# interstage_A1.net
KiCad netlist of a schematic drawn in EAGLE
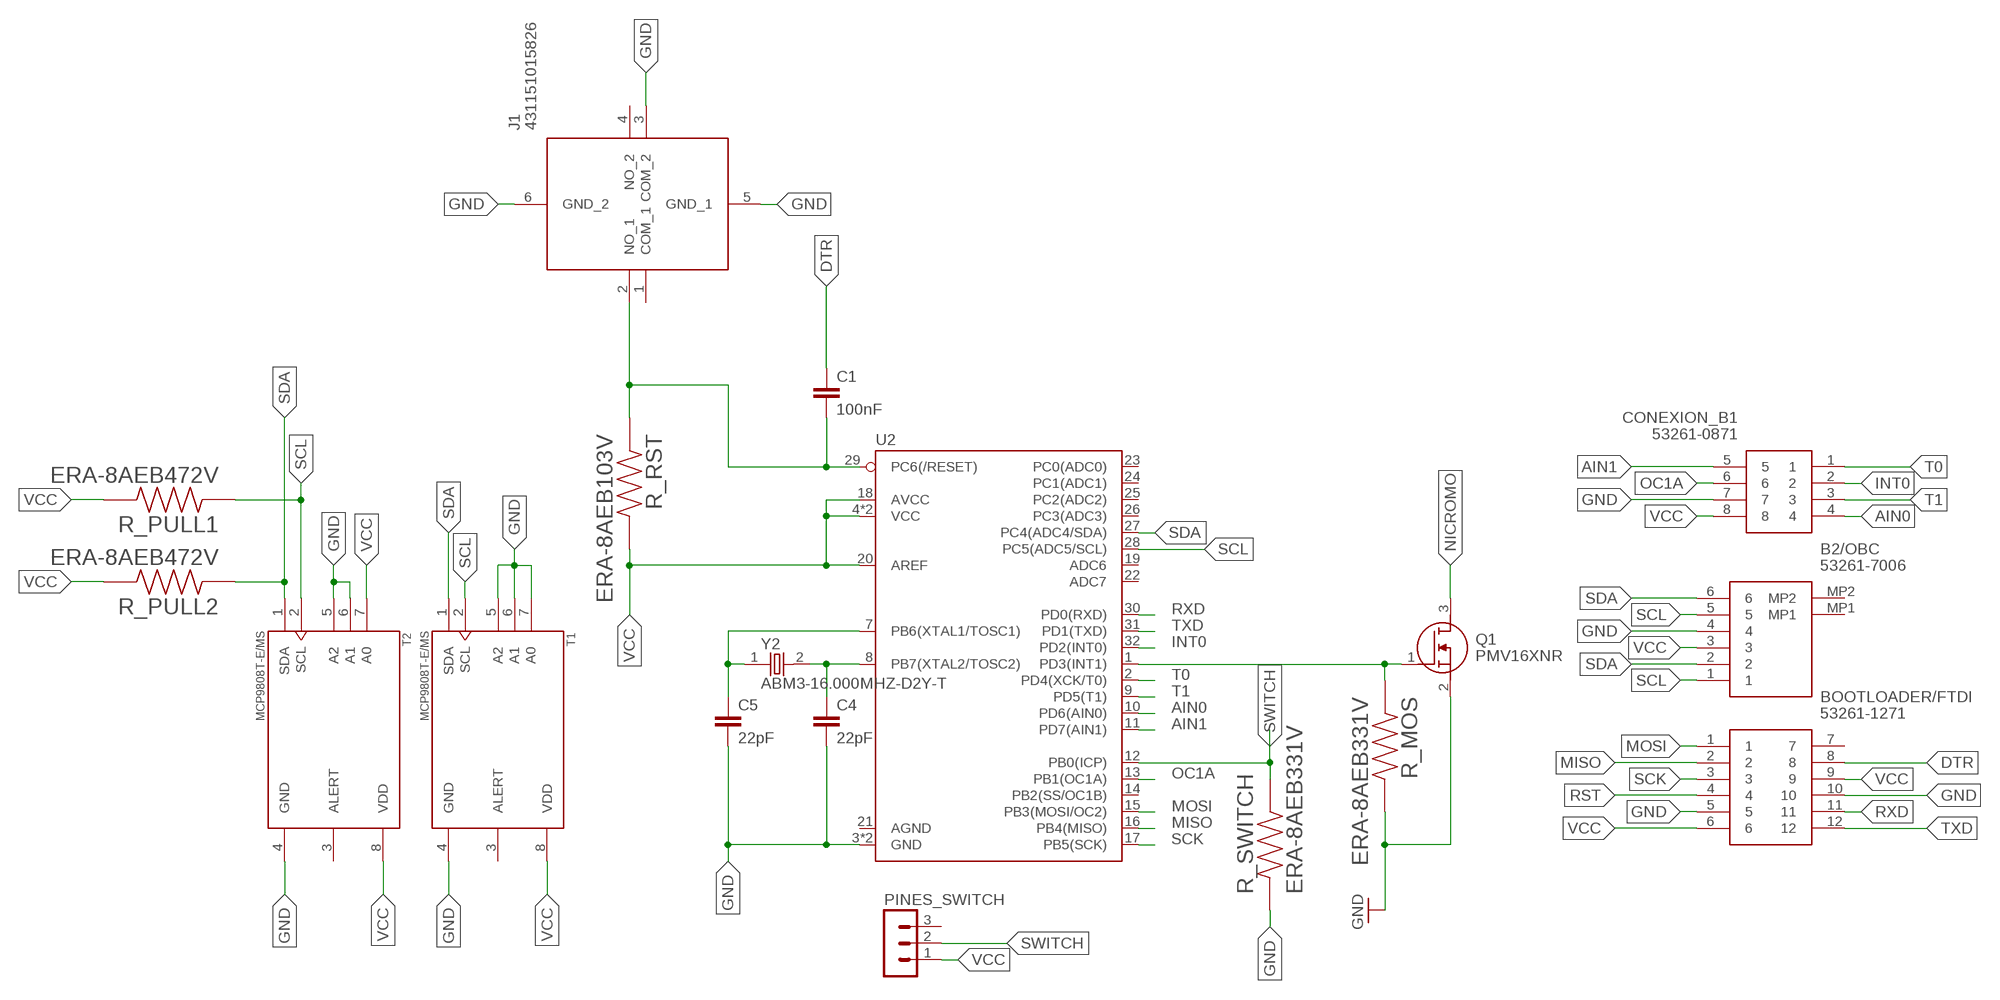
[diagram p0: schematic, sheet 1]

(export (version "E")
  (design (tool "Eeschema 10.0.6"))
  (components
    (comp (ref "B2/OBC")
      (value "53261-7006")
      (footprint "eagle-import:532617006")
      (fields (field (name "MOUSER_PART_NUMBER") "538-53261-7006"))
      (libsource (lib "eagle-import") (part "53261-7006"))
    )
    (comp (ref "BOOTLOADER/FTDI")
      (value "53261-1271")
      (footprint "eagle-import:53261-1271")
      (fields (field (name "MOUSER_PART_NUMBER") "538-53261-1271"))
      (libsource (lib "eagle-import") (part "53261-1271"))
    )
    (comp (ref "C1")
      (value "100nF")
      (footprint "eagle-import:C0805K")
      (libsource (lib "eagle-import") (part "C-EUC0805K"))
    )
    (comp (ref "C4")
      (value "22pF")
      (footprint "eagle-import:C0603K")
      (libsource (lib "eagle-import") (part "C-EUC0603K"))
    )
    (comp (ref "C5")
      (value "22pF")
      (footprint "eagle-import:C0603K")
      (libsource (lib "eagle-import") (part "C-EUC0603K"))
    )
    (comp (ref "CONEXION_B1")
      (value "53261-0871")
      (footprint "eagle-import:53261-0871")
      (fields (field (name "MOUSER_PART_NUMBER") "538-53261-0871"))
      (libsource (lib "eagle-import") (part "53261-0871"))
    )
    (comp (ref "J1")
      (value "431151015826")
      (footprint "eagle-import:431151015826")
      (fields (field (name "MOUSER_PART_NUMBER") "710-431151015826"))
      (libsource (lib "eagle-import") (part "431151015826"))
    )
    (comp (ref "PINES_SWITCH")
      (value "MA03-1")
      (footprint "eagle-import:MA03-1")
      (libsource (lib "eagle-import") (part "MA03-1"))
    )
    (comp (ref "Q1")
      (value "PMV16XNR")
      (footprint "eagle-import:SOT95P230X110-3N")
      (fields (field (name "MOUSER_PART_NUMBER") "771-PMV16XNR"))
      (libsource (lib "eagle-import") (part "PMV16XNR"))
    )
    (comp (ref "R_MOS")
      (value "ERA-8AEB331V")
      (footprint "eagle-import:RESC3216X70N")
      (fields (field (name "DIGI-KEY_PART_NUMBER") "P330BCCT-ND") (field (name "MF") "Panasonic Electronic"))
      (libsource (lib "eagle-import") (part "ERA-8AEB331V"))
    )
    (comp (ref "R_PULL1")
      (value "ERA-8AEB472V")
      (footprint "eagle-import:RESC3216X70N")
      (fields (field (name "DIGI-KEY_PART_NUMBER") "P4.7KBCCT-ND") (field (name "MF") "Panasonic"))
      (libsource (lib "eagle-import") (part "ERA-8AEB472V"))
    )
    (comp (ref "R_PULL2")
      (value "ERA-8AEB472V")
      (footprint "eagle-import:RESC3216X70N")
      (fields (field (name "DIGI-KEY_PART_NUMBER") "P4.7KBCCT-ND") (field (name "MF") "Panasonic"))
      (libsource (lib "eagle-import") (part "ERA-8AEB472V"))
    )
    (comp (ref "R_RST")
      (value "ERA-8AEB103V")
      (footprint "eagle-import:RESC3216X70N")
      (fields
        (field (name "DIGI-KEY_PART_NUMBER") "P10KBCCT-ND")
        (field (name "MF") "Panasonic Electronic Components")
      )
      (libsource (lib "eagle-import") (part "ERA-8AEB103V"))
    )
    (comp (ref "R_SWITCH")
      (value "ERA-8AEB331V")
      (footprint "eagle-import:RESC3216X70N")
      (fields (field (name "DIGI-KEY_PART_NUMBER") "P330BCCT-ND") (field (name "MF") "Panasonic Electronic"))
      (libsource (lib "eagle-import") (part "ERA-8AEB331V"))
    )
    (comp (ref "T1")
      (value "MCP9808T-E/MS")
      (footprint "eagle-import:SOP65P490X110-8N")
      (fields (field (name "DIGI-KEY_PART_NUMBER") "MCP9808T-E/MSCT-ND") (field (name "MF") "Microchip"))
      (libsource (lib "eagle-import") (part "MCP9808T-E/MS"))
    )
    (comp (ref "T2")
      (value "MCP9808T-E/MS")
      (footprint "eagle-import:SOP65P490X110-8N")
      (fields (field (name "DIGI-KEY_PART_NUMBER") "MCP9808T-E/MSCT-ND") (field (name "MF") "Microchip"))
      (libsource (lib "eagle-import") (part "MCP9808T-E/MS"))
    )
    (comp (ref "U2")
      (value "ATMEGA328P_TQFP")
      (footprint "eagle-import:TQFP32-08")
      (libsource (lib "eagle-import") (part "ATMEGA328P_TQFP"))
    )
    (comp (ref "Y2")
      (value "ABM3-16.000MHZ-D2Y-T")
      (footprint "eagle-import:XTAL500X320X130N")
      (fields (field (name "DIGI-KEY_PART_NUMBER") "535-10638-1-ND") (field (name "MF") "Abracon"))
      (libsource (lib "eagle-import") (part "ABM3-16.000MHZ-D2Y-T"))
    )
  )
  (nets
    (net (code "1") (name "AIN0") (class "Default")
      (node (ref "CONEXION_B1") (pin "4") (pinfunction "4_4") (pintype "bidirectional"))
      (node (ref "U2") (pin "10") (pinfunction "PD6(AIN0)_10") (pintype "bidirectional"))
    )
    (net (code "2") (name "AIN1") (class "Default")
      (node (ref "CONEXION_B1") (pin "5") (pinfunction "5_5") (pintype "bidirectional"))
      (node (ref "U2") (pin "11") (pinfunction "PD7(AIN1)_11") (pintype "bidirectional"))
    )
    (net (code "3") (name "DTR") (class "Default")
      (node (ref "BOOTLOADER/FTDI") (pin "8") (pinfunction "8_8") (pintype "bidirectional"))
      (node (ref "C1") (pin "1") (pinfunction "1_1") (pintype "passive"))
    )
    (net (code "4") (name "GND") (class "Default")
      (node (ref "B2/OBC") (pin "4") (pinfunction "4_4") (pintype "bidirectional"))
      (node (ref "BOOTLOADER/FTDI") (pin "10") (pinfunction "10_10") (pintype "bidirectional"))
      (node (ref "BOOTLOADER/FTDI") (pin "5") (pinfunction "5_5") (pintype "bidirectional"))
      (node (ref "C4") (pin "2") (pinfunction "2_2") (pintype "passive"))
      (node (ref "C5") (pin "2") (pinfunction "2_2") (pintype "passive"))
      (node (ref "CONEXION_B1") (pin "7") (pinfunction "7_7") (pintype "bidirectional"))
      (node (ref "J1") (pin "3") (pinfunction "COM_2_3") (pintype "bidirectional"))
      (node (ref "J1") (pin "5") (pinfunction "GND_1_5") (pintype "bidirectional"))
      (node (ref "J1") (pin "6") (pinfunction "GND_2_6") (pintype "bidirectional"))
      (node (ref "Q1") (pin "2") (pinfunction "S_2") (pintype "bidirectional"))
      (node (ref "R_MOS") (pin "2") (pinfunction "2_2") (pintype "passive"))
      (node (ref "R_SWITCH") (pin "1") (pinfunction "1_1") (pintype "passive"))
      (node (ref "T1") (pin "4") (pinfunction "GND_4") (pintype "power_in"))
      (node (ref "T1") (pin "5") (pinfunction "A2_5") (pintype "input"))
      (node (ref "T1") (pin "6") (pinfunction "A1_6") (pintype "input"))
      (node (ref "T1") (pin "7") (pinfunction "A0_7") (pintype "input"))
      (node (ref "T2") (pin "4") (pinfunction "GND_4") (pintype "power_in"))
      (node (ref "T2") (pin "5") (pinfunction "A2_5") (pintype "input"))
      (node (ref "T2") (pin "6") (pinfunction "A1_6") (pintype "input"))
      (node (ref "U2") (pin "3") (pinfunction "GND_3") (pintype "bidirectional"))
      (node (ref "U2") (pin "5") (pinfunction "GND_5") (pintype "bidirectional"))
    )
    (net (code "5") (name "INT0") (class "Default")
      (node (ref "CONEXION_B1") (pin "2") (pinfunction "2_2") (pintype "bidirectional"))
      (node (ref "U2") (pin "32") (pinfunction "PD2(INT0)_32") (pintype "bidirectional"))
    )
    (net (code "6") (name "MISO") (class "Default")
      (node (ref "BOOTLOADER/FTDI") (pin "2") (pinfunction "2_2") (pintype "bidirectional"))
      (node (ref "U2") (pin "16") (pinfunction "PB4(MISO)_16") (pintype "bidirectional"))
    )
    (net (code "7") (name "MOSI") (class "Default")
      (node (ref "BOOTLOADER/FTDI") (pin "1") (pinfunction "1_1") (pintype "bidirectional"))
      (node (ref "U2") (pin "15") (pinfunction "PB3(MOSI/OC2)_15") (pintype "bidirectional"))
    )
    (net (code "8") (name "NICROMO") (class "Default")
      (node (ref "Q1") (pin "3") (pinfunction "D_3") (pintype "bidirectional"))
    )
    (net (code "9") (name "Net-(Q1-G)") (class "Default")
      (node (ref "Q1") (pin "1") (pinfunction "G_1") (pintype "bidirectional"))
      (node (ref "R_MOS") (pin "1") (pinfunction "1_1") (pintype "passive"))
      (node (ref "U2") (pin "1") (pinfunction "PD3(INT1)_1") (pintype "bidirectional"))
    )
    (net (code "10") (name "Net-(U2-PB6(XTAL1{slash}TOSC1))") (class "Default")
      (node (ref "C5") (pin "1") (pinfunction "1_1") (pintype "passive"))
      (node (ref "U2") (pin "7") (pinfunction "PB6(XTAL1/TOSC1)_7") (pintype "bidirectional"))
      (node (ref "Y2") (pin "1") (pinfunction "1_1") (pintype "passive"))
    )
    (net (code "11") (name "Net-(U2-PB7(XTAL2{slash}TOSC2))") (class "Default")
      (node (ref "C4") (pin "1") (pinfunction "1_1") (pintype "passive"))
      (node (ref "U2") (pin "8") (pinfunction "PB7(XTAL2/TOSC2)_8") (pintype "bidirectional"))
      (node (ref "Y2") (pin "2") (pinfunction "2_2") (pintype "passive"))
    )
    (net (code "12") (name "OC1A") (class "Default")
      (node (ref "CONEXION_B1") (pin "6") (pinfunction "6_6") (pintype "bidirectional"))
      (node (ref "U2") (pin "13") (pinfunction "PB1(OC1A)_13") (pintype "bidirectional"))
    )
    (net (code "13") (name "RST") (class "Default")
      (node (ref "BOOTLOADER/FTDI") (pin "4") (pinfunction "4_4") (pintype "bidirectional"))
      (node (ref "C1") (pin "2") (pinfunction "2_2") (pintype "passive"))
      (node (ref "J1") (pin "2") (pinfunction "NO_1_2") (pintype "bidirectional"))
      (node (ref "R_RST") (pin "1") (pinfunction "1_1") (pintype "passive"))
      (node (ref "U2") (pin "29") (pinfunction "PC6(/RESET)_29") (pintype "bidirectional"))
    )
    (net (code "14") (name "RXD") (class "Default")
      (node (ref "BOOTLOADER/FTDI") (pin "11") (pinfunction "11_11") (pintype "bidirectional"))
      (node (ref "U2") (pin "30") (pinfunction "PD0(RXD)_30") (pintype "bidirectional"))
    )
    (net (code "15") (name "SCK") (class "Default")
      (node (ref "BOOTLOADER/FTDI") (pin "3") (pinfunction "3_3") (pintype "bidirectional"))
      (node (ref "U2") (pin "17") (pinfunction "PB5(SCK)_17") (pintype "bidirectional"))
    )
    (net (code "16") (name "SCL") (class "Default")
      (node (ref "B2/OBC") (pin "1") (pinfunction "1_1") (pintype "bidirectional"))
      (node (ref "B2/OBC") (pin "5") (pinfunction "5_5") (pintype "bidirectional"))
      (node (ref "R_PULL1") (pin "1") (pinfunction "1_1") (pintype "passive"))
      (node (ref "T1") (pin "2") (pinfunction "SCL_2") (pintype "input"))
      (node (ref "T2") (pin "2") (pinfunction "SCL_2") (pintype "input"))
      (node (ref "U2") (pin "28") (pinfunction "PC5(ADC5/SCL)_28") (pintype "bidirectional"))
    )
    (net (code "17") (name "SDA") (class "Default")
      (node (ref "B2/OBC") (pin "2") (pinfunction "2_2") (pintype "bidirectional"))
      (node (ref "B2/OBC") (pin "6") (pinfunction "6_6") (pintype "bidirectional"))
      (node (ref "R_PULL2") (pin "1") (pinfunction "1_1") (pintype "passive"))
      (node (ref "T1") (pin "1") (pinfunction "SDA_1") (pintype "bidirectional"))
      (node (ref "T2") (pin "1") (pinfunction "SDA_1") (pintype "bidirectional"))
      (node (ref "U2") (pin "27") (pinfunction "PC4(ADC4/SDA)_27") (pintype "bidirectional"))
    )
    (net (code "18") (name "SWITCH") (class "Default")
      (node (ref "PINES_SWITCH") (pin "2") (pinfunction "2_2") (pintype "passive"))
      (node (ref "R_SWITCH") (pin "2") (pinfunction "2_2") (pintype "passive"))
      (node (ref "U2") (pin "12") (pinfunction "PB0(ICP)_12") (pintype "bidirectional"))
    )
    (net (code "19") (name "T0") (class "Default")
      (node (ref "CONEXION_B1") (pin "1") (pinfunction "1_1") (pintype "bidirectional"))
      (node (ref "U2") (pin "2") (pinfunction "PD4(XCK/T0)_2") (pintype "bidirectional"))
    )
    (net (code "20") (name "T1") (class "Default")
      (node (ref "CONEXION_B1") (pin "3") (pinfunction "3_3") (pintype "bidirectional"))
      (node (ref "U2") (pin "9") (pinfunction "PD5(T1)_9") (pintype "bidirectional"))
    )
    (net (code "21") (name "TXD") (class "Default")
      (node (ref "BOOTLOADER/FTDI") (pin "12") (pinfunction "12_12") (pintype "bidirectional"))
      (node (ref "U2") (pin "31") (pinfunction "PD1(TXD)_31") (pintype "bidirectional"))
    )
    (net (code "22") (name "VCC") (class "Default")
      (node (ref "B2/OBC") (pin "3") (pinfunction "3_3") (pintype "bidirectional"))
      (node (ref "BOOTLOADER/FTDI") (pin "6") (pinfunction "6_6") (pintype "bidirectional"))
      (node (ref "BOOTLOADER/FTDI") (pin "9") (pinfunction "9_9") (pintype "bidirectional"))
      (node (ref "CONEXION_B1") (pin "8") (pinfunction "8_8") (pintype "bidirectional"))
      (node (ref "PINES_SWITCH") (pin "1") (pinfunction "1_1") (pintype "passive"))
      (node (ref "R_PULL1") (pin "2") (pinfunction "2_2") (pintype "passive"))
      (node (ref "R_PULL2") (pin "2") (pinfunction "2_2") (pintype "passive"))
      (node (ref "R_RST") (pin "2") (pinfunction "2_2") (pintype "passive"))
      (node (ref "T1") (pin "8") (pinfunction "VDD_8") (pintype "power_in"))
      (node (ref "T2") (pin "7") (pinfunction "A0_7") (pintype "input"))
      (node (ref "T2") (pin "8") (pinfunction "VDD_8") (pintype "power_in"))
      (node (ref "U2") (pin "18") (pinfunction "AVCC_18") (pintype "bidirectional"))
      (node (ref "U2") (pin "20") (pinfunction "AREF_20") (pintype "bidirectional"))
      (node (ref "U2") (pin "4") (pinfunction "VCC_4") (pintype "bidirectional"))
      (node (ref "U2") (pin "6") (pinfunction "VCC_6") (pintype "bidirectional"))
    )
    (net (code "23") (name "unconnected-(B2/OBC-PadMP1)") (class "Default")
      (node (ref "B2/OBC") (pin "MP1") (pinfunction "MP1_MP1") (pintype "bidirectional"))
    )
    (net (code "24") (name "unconnected-(B2/OBC-PadMP2)") (class "Default")
      (node (ref "B2/OBC") (pin "MP2") (pinfunction "MP2_MP2") (pintype "bidirectional"))
    )
    (net (code "25") (name "unconnected-(BOOTLOADER/FTDI-Pad7)") (class "Default")
      (node (ref "BOOTLOADER/FTDI") (pin "7") (pinfunction "7_7") (pintype "bidirectional"))
    )
    (net (code "26") (name "unconnected-(J1-COM_1-Pad1)") (class "Default")
      (node (ref "J1") (pin "1") (pinfunction "COM_1_1") (pintype "bidirectional"))
    )
    (net (code "27") (name "unconnected-(J1-NO_2-Pad4)") (class "Default")
      (node (ref "J1") (pin "4") (pinfunction "NO_2_4") (pintype "bidirectional"))
    )
    (net (code "28") (name "unconnected-(PINES_SWITCH-Pad3)") (class "Default")
      (node (ref "PINES_SWITCH") (pin "3") (pinfunction "3_3") (pintype "passive"))
    )
    (net (code "29") (name "unconnected-(T1-ALERT-Pad3)") (class "Default")
      (node (ref "T1") (pin "3") (pinfunction "ALERT_3") (pintype "output"))
    )
    (net (code "30") (name "unconnected-(T2-ALERT-Pad3)") (class "Default")
      (node (ref "T2") (pin "3") (pinfunction "ALERT_3") (pintype "output"))
    )
    (net (code "31") (name "unconnected-(U2-ADC6-Pad19)") (class "Default")
      (node (ref "U2") (pin "19") (pinfunction "ADC6_19") (pintype "bidirectional"))
    )
    (net (code "32") (name "unconnected-(U2-ADC7-Pad22)") (class "Default")
      (node (ref "U2") (pin "22") (pinfunction "ADC7_22") (pintype "bidirectional"))
    )
    (net (code "33") (name "unconnected-(U2-AGND-Pad21)") (class "Default")
      (node (ref "U2") (pin "21") (pinfunction "AGND_21") (pintype "bidirectional"))
    )
    (net (code "34") (name "unconnected-(U2-PB2(SS{slash}OC1B)-Pad14)") (class "Default")
      (node (ref "U2") (pin "14") (pinfunction "PB2(SS/OC1B)_14") (pintype "bidirectional"))
    )
    (net (code "35") (name "unconnected-(U2-PC0(ADC0)-Pad23)") (class "Default")
      (node (ref "U2") (pin "23") (pinfunction "PC0(ADC0)_23") (pintype "bidirectional"))
    )
    (net (code "36") (name "unconnected-(U2-PC1(ADC1)-Pad24)") (class "Default")
      (node (ref "U2") (pin "24") (pinfunction "PC1(ADC1)_24") (pintype "bidirectional"))
    )
    (net (code "37") (name "unconnected-(U2-PC2(ADC2)-Pad25)") (class "Default")
      (node (ref "U2") (pin "25") (pinfunction "PC2(ADC2)_25") (pintype "bidirectional"))
    )
    (net (code "38") (name "unconnected-(U2-PC3(ADC3)-Pad26)") (class "Default")
      (node (ref "U2") (pin "26") (pinfunction "PC3(ADC3)_26") (pintype "bidirectional"))
    )
  )
)
